# delay.net
KiCad netlist of a schematic drawn in EAGLE
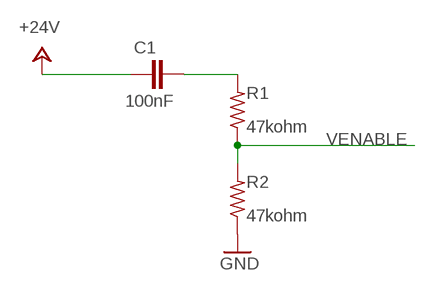
[diagram p0: schematic, sheet 1]

(export (version "E")
  (design (tool "Eeschema 10.0.6"))
  (components
    (comp (ref "C1")
      (value "100nF")
      (footprint "eagle-import:C025-025X050")
      (libsource (lib "eagle-import") (part "C-EU025-025X050"))
    )
    (comp (ref "R1")
      (value "47kohm")
      (footprint "eagle-import:0207_10")
      (libsource (lib "eagle-import") (part "R-US_0207/10"))
    )
    (comp (ref "R2")
      (value "47kohm")
      (footprint "eagle-import:0207_10")
      (libsource (lib "eagle-import") (part "R-US_0207/10"))
    )
  )
  (nets
    (net (code "1") (name "+24V") (class "Default")
      (node (ref "C1") (pin "1") (pinfunction "1_1") (pintype "passive"))
    )
    (net (code "2") (name "/VENABLE") (class "Default")
      (node (ref "R1") (pin "1") (pinfunction "1_1") (pintype "passive"))
      (node (ref "R2") (pin "2") (pinfunction "2_2") (pintype "passive"))
    )
    (net (code "3") (name "GND") (class "Default")
      (node (ref "R2") (pin "1") (pinfunction "1_1") (pintype "passive"))
    )
    (net (code "4") (name "Net-(C1-Pad2)") (class "Default")
      (node (ref "C1") (pin "2") (pinfunction "2_2") (pintype "passive"))
      (node (ref "R1") (pin "2") (pinfunction "2_2") (pintype "passive"))
    )
  )
)
